# TCAN1146_PINOUT.net
KiCad netlist of a schematic drawn in Altium Designer
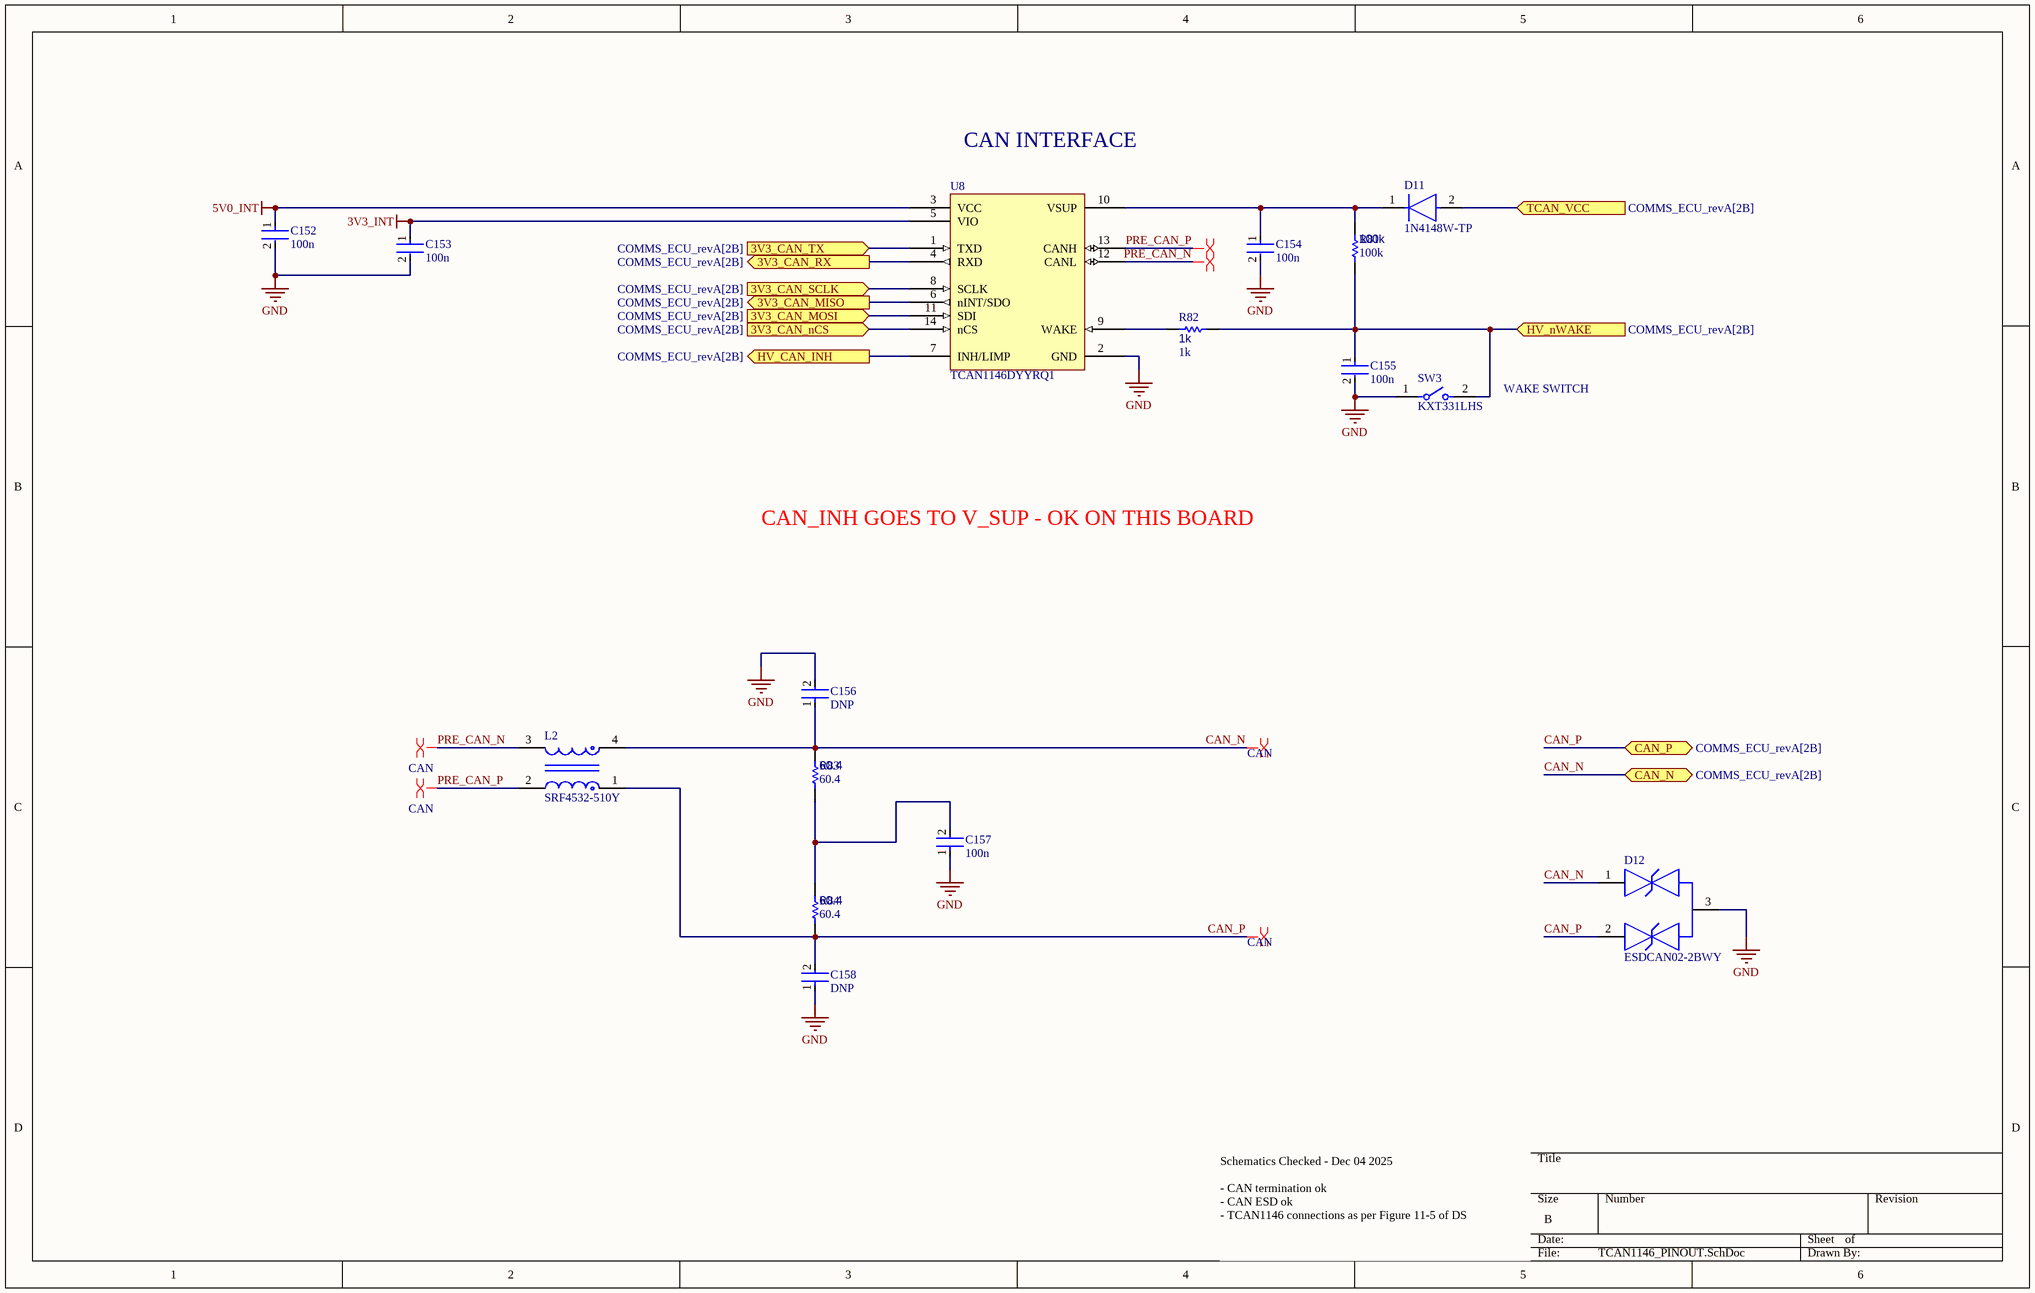
[diagram p0: TCAN1146_PINOUT.SchDoc]

(export (version "E")
  (design (tool "Eeschema 10.0.6"))
  (components
    (comp (ref "C152")
      (value "100n")
      (footprint "FP-0402-L_1_0_0_05-W_0_5-IPC_A")
      (description "LARGE PADS, 0402 CAP, CHANGE COMMENT TO MATCH REAL P/N")
      (libsource (lib "Space Concordia") (part "b4654b650e69147ec39a6b967a45e02"))
    )
    (comp (ref "C153")
      (value "100n")
      (footprint "FP-0402-L_1_0_0_05-W_0_5-IPC_A")
      (description "LARGE PADS, 0402 CAP, CHANGE COMMENT TO MATCH REAL P/N")
      (libsource (lib "Space Concordia") (part "b4654b650e69147ec39a6b967a45e02"))
    )
    (comp (ref "C154")
      (value "100n")
      (footprint "FP-0402-L_1_0_0_05-W_0_5-IPC_A")
      (description "LARGE PADS, 0402 CAP, CHANGE COMMENT TO MATCH REAL P/N")
      (libsource (lib "Space Concordia") (part "b4654b650e69147ec39a6b967a45e02"))
    )
    (comp (ref "C155")
      (value "100n")
      (footprint "FP-0402-L_1_0_0_05-W_0_5-IPC_A")
      (description "LARGE PADS, 0402 CAP, CHANGE COMMENT TO MATCH REAL P/N")
      (libsource (lib "Space Concordia") (part "b4654b650e69147ec39a6b967a45e02"))
    )
    (comp (ref "C156")
      (value "DNP")
      (footprint "FP-0402-L_1_0_0_05-W_0_5-IPC_A")
      (description "LARGE PADS, 0402 CAP, CHANGE COMMENT TO MATCH REAL P/N")
      (libsource (lib "Space Concordia") (part "b4654b650e69147ec39a6b967a45e02"))
    )
    (comp (ref "C157")
      (value "100n")
      (footprint "FP-0402-L_1_0_0_05-W_0_5-IPC_A")
      (description "LARGE PADS, 0402 CAP, CHANGE COMMENT TO MATCH REAL P/N")
      (libsource (lib "Space Concordia") (part "b4654b650e69147ec39a6b967a45e02"))
    )
    (comp (ref "C158")
      (value "DNP")
      (footprint "FP-0402-L_1_0_0_05-W_0_5-IPC_A")
      (description "LARGE PADS, 0402 CAP, CHANGE COMMENT TO MATCH REAL P/N")
      (libsource (lib "Space Concordia") (part "b4654b650e69147ec39a6b967a45e02"))
    )
    (comp (ref "D11")
      (value "1N4148W-TP")
      (footprint "FP-SOD-123-IPC_A")
      (description "DIODE GEN PURP 100V 150MA SOD123")
      (libsource (lib "Altium Content Vault") (part "d7152d700b627762746794eb795d46e"))
    )
    (comp (ref "D12")
      (value "ESDCAN02-2BWY")
      (footprint "FP-SOT323-3L-MFG")
      (description "TVS DIODE 26.5V 44V SOT323-3")
      (fields
        (field (name "MANUFACTURER") "STMicroelectronics")
        (field (name "OCTOPART") "https://octopart.com/esdcan02-2bwy-stmicroelectronics-58631133")
      )
      (libsource (lib "Altium Content Vault") (part "0b9019fb5e52ed66df21ec1535be59d"))
    )
    (comp (ref "L2")
      (value "SRF4532-510Y")
      (footprint "FP-SRF4532-MFG")
      (description "CMC 51UH 200MA 2LN 2KOHM SMD")
      (fields (field (name "TOLERANCE") "50%"))
      (libsource (lib "Altium Content Vault") (part "aca3f6a10b859f211cca95010157f3b"))
    )
    (comp (ref "R81")
      (value "100k")
      (footprint "R0603B")
      (description "Resistor")
      (fields (field (name "ALTIUM_VALUE") "100k"))
      (libsource (lib "Space Concordia") (part "Resistor"))
    )
    (comp (ref "R82")
      (value "1k")
      (footprint "R0603B")
      (description "Resistor")
      (fields (field (name "ALTIUM_VALUE") "1k"))
      (libsource (lib "Space Concordia") (part "Resistor"))
    )
    (comp (ref "R83")
      (value "60.4")
      (footprint "R0603B")
      (description "Resistor")
      (fields (field (name "ALTIUM_VALUE") "60.4"))
      (libsource (lib "Space Concordia") (part "Resistor"))
    )
    (comp (ref "R84")
      (value "60.4")
      (footprint "R0603B")
      (description "Resistor")
      (fields (field (name "ALTIUM_VALUE") "60.4"))
      (libsource (lib "Space Concordia") (part "Resistor"))
    )
    (comp (ref "SW3")
      (value "KXT331LHS")
      (footprint "FP-KXT331LHS-MFG")
      (description "SWITCH TACTILE SPST-NO 0.02A 15V")
      (libsource (lib "Altium Content Vault") (part "bb27bde45df87f1f469753f287ef5ae"))
    )
    (comp (ref "U8")
      (value "TCAN1146DYYRQ1")
      (footprint "TCAN1146DYYRQ1-Footprint-1")
      (libsource (lib "Space Concordia") (part "CMP-015-00012-2"))
    )
  )
  (nets
    (net (code "1") (name "/3V3_CAN_MISO") (class "Default")
      (node (ref "U8") (pin "6") (pinfunction "nINT/SDO_6") (pintype "output"))
    )
    (net (code "2") (name "/3V3_CAN_MOSI") (class "Default")
      (node (ref "U8") (pin "11") (pinfunction "SDI_11") (pintype "input"))
    )
    (net (code "3") (name "/3V3_CAN_RX") (class "Default")
      (node (ref "U8") (pin "4") (pinfunction "RXD_4") (pintype "output"))
    )
    (net (code "4") (name "/3V3_CAN_SCLK") (class "Default")
      (node (ref "U8") (pin "8") (pinfunction "SCLK_8") (pintype "input"))
    )
    (net (code "5") (name "/3V3_CAN_TX") (class "Default")
      (node (ref "U8") (pin "1") (pinfunction "TXD_1") (pintype "input"))
    )
    (net (code "6") (name "/3V3_CAN_nCS") (class "Default")
      (node (ref "U8") (pin "14") (pinfunction "nCS_14") (pintype "input"))
    )
    (net (code "7") (name "/CAN_N") (class "Default")
      (node (ref "C156") (pin "1") (pinfunction "1_1") (pintype "passive"))
      (node (ref "D12") (pin "1") (pinfunction "1_1") (pintype "passive"))
      (node (ref "L2") (pin "4") (pinfunction "4_4") (pintype "passive"))
      (node (ref "R83") (pin "2") (pinfunction "2_2") (pintype "passive"))
    )
    (net (code "8") (name "/CAN_P") (class "Default")
      (node (ref "C158") (pin "2") (pinfunction "2_2") (pintype "passive"))
      (node (ref "D12") (pin "2") (pinfunction "2_2") (pintype "passive"))
      (node (ref "L2") (pin "1") (pinfunction "1_1") (pintype "passive"))
      (node (ref "R84") (pin "1") (pinfunction "1_1") (pintype "passive"))
    )
    (net (code "9") (name "/HV_CAN_INH") (class "Default")
      (node (ref "U8") (pin "7") (pinfunction "INH/LIMP_7") (pintype "passive"))
    )
    (net (code "10") (name "/HV_nWAKE") (class "Default")
      (node (ref "C155") (pin "1") (pinfunction "1_1") (pintype "passive"))
      (node (ref "R81") (pin "1") (pinfunction "1_1") (pintype "passive"))
      (node (ref "R82") (pin "2") (pinfunction "2_2") (pintype "passive"))
      (node (ref "SW3") (pin "2") (pinfunction "2_2") (pintype "passive"))
    )
    (net (code "11") (name "/PRE_CAN_N") (class "Default")
      (node (ref "L2") (pin "3") (pinfunction "3_3") (pintype "passive"))
      (node (ref "U8") (pin "12") (pinfunction "CANL_12") (pintype "bidirectional"))
    )
    (net (code "12") (name "/PRE_CAN_P") (class "Default")
      (node (ref "L2") (pin "2") (pinfunction "2_2") (pintype "passive"))
      (node (ref "U8") (pin "13") (pinfunction "CANH_13") (pintype "bidirectional"))
    )
    (net (code "13") (name "/TCAN_VCC") (class "Default")
      (node (ref "D11") (pin "2") (pinfunction "A_2") (pintype "passive"))
    )
    (net (code "14") (name "3V3_INT") (class "Default")
      (node (ref "C153") (pin "1") (pinfunction "1_1") (pintype "passive"))
      (node (ref "U8") (pin "5") (pinfunction "VIO_5") (pintype "power_in"))
    )
    (net (code "15") (name "5V0_INT") (class "Default")
      (node (ref "C152") (pin "1") (pinfunction "1_1") (pintype "passive"))
      (node (ref "U8") (pin "3") (pinfunction "VCC_3") (pintype "power_in"))
    )
    (net (code "16") (name "GND") (class "Default")
      (node (ref "C152") (pin "2") (pinfunction "2_2") (pintype "passive"))
      (node (ref "C153") (pin "2") (pinfunction "2_2") (pintype "passive"))
      (node (ref "C154") (pin "2") (pinfunction "2_2") (pintype "passive"))
      (node (ref "C155") (pin "2") (pinfunction "2_2") (pintype "passive"))
      (node (ref "C156") (pin "2") (pinfunction "2_2") (pintype "passive"))
      (node (ref "C157") (pin "1") (pinfunction "1_1") (pintype "passive"))
      (node (ref "C158") (pin "1") (pinfunction "1_1") (pintype "passive"))
      (node (ref "D12") (pin "3") (pinfunction "3_3") (pintype "passive"))
      (node (ref "SW3") (pin "1") (pinfunction "1_1") (pintype "passive"))
      (node (ref "U8") (pin "2") (pinfunction "GND_2") (pintype "power_in"))
    )
    (net (code "17") (name "Net-(C157-Pad2)") (class "Default")
      (node (ref "C157") (pin "2") (pinfunction "2_2") (pintype "passive"))
      (node (ref "R83") (pin "1") (pinfunction "1_1") (pintype "passive"))
      (node (ref "R84") (pin "2") (pinfunction "2_2") (pintype "passive"))
    )
    (net (code "18") (name "Net-(D11-C)") (class "Default")
      (node (ref "C154") (pin "1") (pinfunction "1_1") (pintype "passive"))
      (node (ref "D11") (pin "1") (pinfunction "C_1") (pintype "passive"))
      (node (ref "R81") (pin "2") (pinfunction "2_2") (pintype "passive"))
      (node (ref "U8") (pin "10") (pinfunction "VSUP_10") (pintype "power_in"))
    )
    (net (code "19") (name "Net-(U8-WAKE)") (class "Default")
      (node (ref "R82") (pin "1") (pinfunction "1_1") (pintype "passive"))
      (node (ref "U8") (pin "9") (pinfunction "WAKE_9") (pintype "input"))
    )
  )
)
